# TinyTony_ShenzenReady.net
KiCad netlist of a schematic drawn in EAGLE
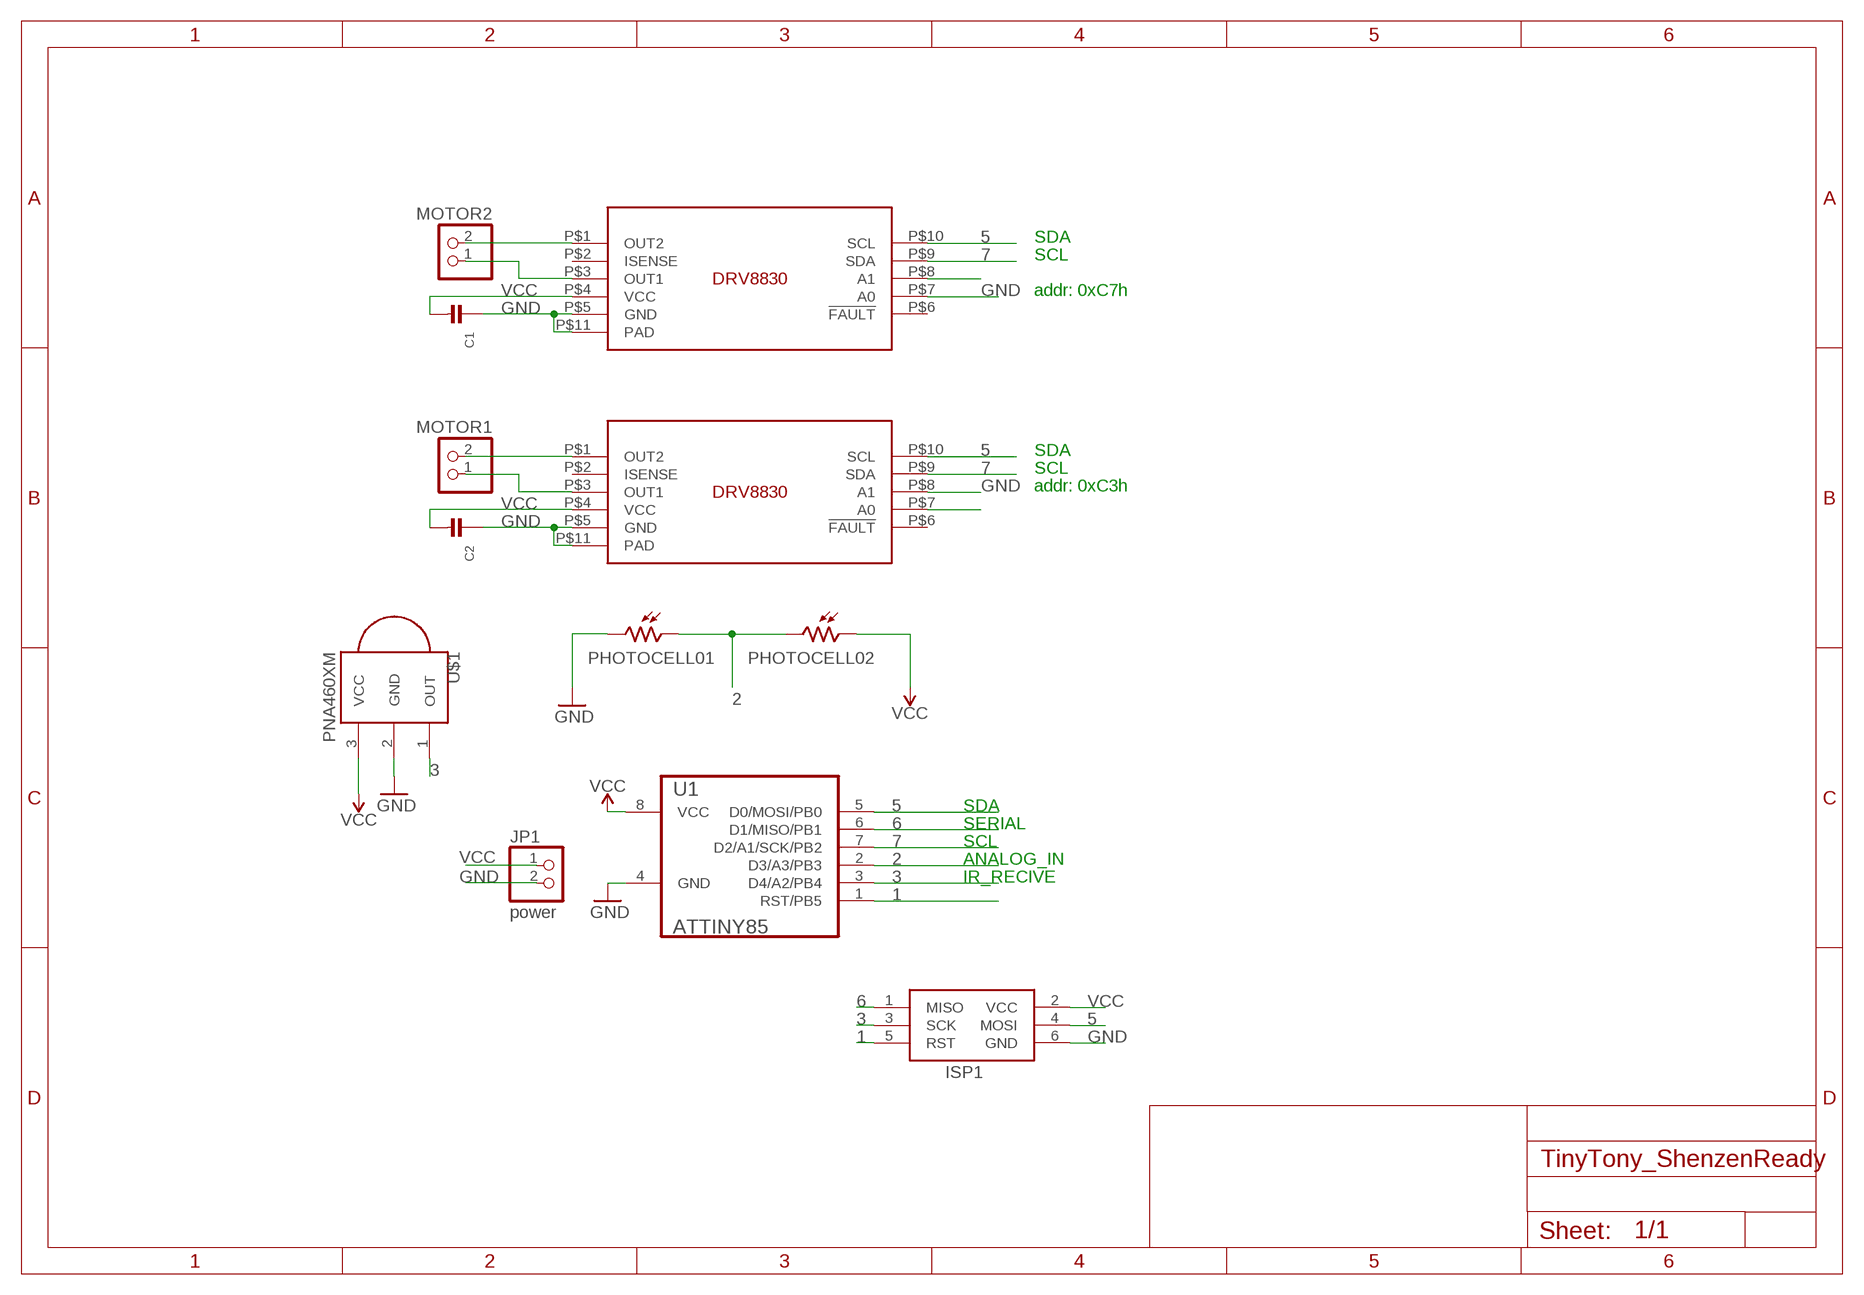
[diagram p0: schematic, sheet 1]

(export (version "E")
  (design (tool "Eeschema 10.0.6"))
  (components
    (comp (ref "C1")
      (value "CAP_CERAMIC1206")
      (footprint "eagle-import:1206")
      (libsource (lib "eagle-import") (part "CAP_CERAMIC1206"))
    )
    (comp (ref "C2")
      (value "CAP_CERAMIC1206")
      (footprint "eagle-import:1206")
      (libsource (lib "eagle-import") (part "CAP_CERAMIC1206"))
    )
    (comp (ref "ISP1")
      (value "AVRISPPOGO")
      (footprint "eagle-import:AVRISP-50MIL")
      (libsource (lib "eagle-import") (part "AVRISPPOGO"))
    )
    (comp (ref "JP1")
      (value "power")
      (footprint "eagle-import:1X02_ROUND")
      (libsource (lib "eagle-import") (part "HEADER-1X2ROUND"))
    )
    (comp (ref "JP2")
      (value "MOTOR1")
      (footprint "eagle-import:1X02_ROUND")
      (libsource (lib "eagle-import") (part "HEADER-1X2ROUND"))
    )
    (comp (ref "JP3")
      (value "MOTOR2")
      (footprint "eagle-import:1X02_ROUND")
      (libsource (lib "eagle-import") (part "HEADER-1X2ROUND"))
    )
    (comp (ref "PHOTOCELL01")
      (value "PHOTOCELL0N1")
      (footprint "eagle-import:TO46-VT200")
      (libsource (lib "eagle-import") (part "PHOTOCELL0N1"))
    )
    (comp (ref "PHOTOCELL02")
      (value "PHOTOCELL0N1")
      (footprint "eagle-import:TO46-VT200")
      (libsource (lib "eagle-import") (part "PHOTOCELL0N1"))
    )
    (comp (ref "U$1")
      (value "PNA460XM")
      (footprint "eagle-import:PNA460XM")
      (libsource (lib "eagle-import") (part "PNA460XM"))
    )
    (comp (ref "U$2")
      (value "DRV8830")
      (footprint "eagle-import:DRV8830")
      (libsource (lib "eagle-import") (part "DRV8830"))
    )
    (comp (ref "U$3")
      (value "DRV8830")
      (footprint "eagle-import:DRV8830")
      (libsource (lib "eagle-import") (part "DRV8830"))
    )
    (comp (ref "U1")
      (value "ATTINY85")
      (footprint "eagle-import:SOIC127P798X216-8N")
      (fields (field (name "MPN") "ATTINY85-20SU"))
      (libsource (lib "eagle-import") (part "ATTINY85-20SU"))
    )
  )
  (nets
    (net (code "1") (name "/1") (class "Default")
      (node (ref "ISP1") (pin "5") (pinfunction "RST_5") (pintype "output"))
      (node (ref "U1") (pin "1") (pinfunction "RST/PB5_1") (pintype "bidirectional"))
    )
    (net (code "2") (name "/2") (class "Default")
      (node (ref "PHOTOCELL01") (pin "1") (pinfunction "1_1") (pintype "passive"))
      (node (ref "PHOTOCELL02") (pin "2") (pinfunction "2_2") (pintype "passive"))
      (node (ref "U1") (pin "2") (pinfunction "D3/A3/PB3_2") (pintype "bidirectional"))
    )
    (net (code "3") (name "/3") (class "Default")
      (node (ref "ISP1") (pin "3") (pinfunction "SCK_3") (pintype "output"))
      (node (ref "U$1") (pin "1") (pinfunction "OUT_1") (pintype "output"))
      (node (ref "U1") (pin "3") (pinfunction "D4/A2/PB4_3") (pintype "bidirectional"))
    )
    (net (code "4") (name "/5") (class "Default")
      (node (ref "ISP1") (pin "4") (pinfunction "MOSI_4") (pintype "output"))
      (node (ref "U$2") (pin "P$10") (pinfunction "SCL_P$10") (pintype "bidirectional"))
      (node (ref "U$3") (pin "P$10") (pinfunction "SCL_P$10") (pintype "bidirectional"))
      (node (ref "U1") (pin "5") (pinfunction "D0/MOSI/PB0_5") (pintype "bidirectional"))
    )
    (net (code "5") (name "/6") (class "Default")
      (node (ref "ISP1") (pin "1") (pinfunction "MISO_1") (pintype "input"))
      (node (ref "U1") (pin "6") (pinfunction "D1/MISO/PB1_6") (pintype "bidirectional"))
    )
    (net (code "6") (name "/7") (class "Default")
      (node (ref "U$2") (pin "P$9") (pinfunction "SDA_P$9") (pintype "bidirectional"))
      (node (ref "U$3") (pin "P$9") (pinfunction "SDA_P$9") (pintype "bidirectional"))
      (node (ref "U1") (pin "7") (pinfunction "D2/A1/SCK/PB2_7") (pintype "bidirectional"))
    )
    (net (code "7") (name "GND") (class "Default")
      (node (ref "C1") (pin "1") (pinfunction "P$1_1") (pintype "passive"))
      (node (ref "C2") (pin "1") (pinfunction "P$1_1") (pintype "passive"))
      (node (ref "ISP1") (pin "6") (pinfunction "GND_6") (pintype "power_in"))
      (node (ref "JP1") (pin "2") (pinfunction "2_2") (pintype "passive"))
      (node (ref "PHOTOCELL01") (pin "2") (pinfunction "2_2") (pintype "passive"))
      (node (ref "U$1") (pin "2") (pinfunction "GND_2") (pintype "power_in"))
      (node (ref "U$2") (pin "P$11") (pinfunction "PAD_P$11") (pintype "bidirectional"))
      (node (ref "U$2") (pin "P$5") (pinfunction "GND_P$5") (pintype "bidirectional"))
      (node (ref "U$2") (pin "P$8") (pinfunction "A1_P$8") (pintype "bidirectional"))
      (node (ref "U$3") (pin "P$11") (pinfunction "PAD_P$11") (pintype "bidirectional"))
      (node (ref "U$3") (pin "P$5") (pinfunction "GND_P$5") (pintype "bidirectional"))
      (node (ref "U$3") (pin "P$7") (pinfunction "A0_P$7") (pintype "bidirectional"))
      (node (ref "U1") (pin "4") (pinfunction "GND_4") (pintype "passive"))
    )
    (net (code "8") (name "Net-(U$2-OUT1)") (class "Default")
      (node (ref "JP2") (pin "1") (pinfunction "1_1") (pintype "passive"))
      (node (ref "U$2") (pin "P$3") (pinfunction "OUT1_P$3") (pintype "bidirectional"))
    )
    (net (code "9") (name "Net-(U$2-OUT2)") (class "Default")
      (node (ref "JP2") (pin "2") (pinfunction "2_2") (pintype "passive"))
      (node (ref "U$2") (pin "P$1") (pinfunction "OUT2_P$1") (pintype "bidirectional"))
    )
    (net (code "10") (name "Net-(U$3-OUT1)") (class "Default")
      (node (ref "JP3") (pin "1") (pinfunction "1_1") (pintype "passive"))
      (node (ref "U$3") (pin "P$3") (pinfunction "OUT1_P$3") (pintype "bidirectional"))
    )
    (net (code "11") (name "Net-(U$3-OUT2)") (class "Default")
      (node (ref "JP3") (pin "2") (pinfunction "2_2") (pintype "passive"))
      (node (ref "U$3") (pin "P$1") (pinfunction "OUT2_P$1") (pintype "bidirectional"))
    )
    (net (code "12") (name "VCC") (class "Default")
      (node (ref "C1") (pin "2") (pinfunction "P$2_2") (pintype "passive"))
      (node (ref "C2") (pin "2") (pinfunction "P$2_2") (pintype "passive"))
      (node (ref "ISP1") (pin "2") (pinfunction "VCC_2") (pintype "power_in"))
      (node (ref "JP1") (pin "1") (pinfunction "1_1") (pintype "passive"))
      (node (ref "PHOTOCELL02") (pin "1") (pinfunction "1_1") (pintype "passive"))
      (node (ref "U$1") (pin "3") (pinfunction "VCC_3") (pintype "power_in"))
      (node (ref "U$2") (pin "P$4") (pinfunction "VCC_P$4") (pintype "bidirectional"))
      (node (ref "U$3") (pin "P$4") (pinfunction "VCC_P$4") (pintype "bidirectional"))
      (node (ref "U1") (pin "8") (pinfunction "VCC_8") (pintype "power_in"))
    )
    (net (code "13") (name "unconnected-(U$2-A0-PadP$7)") (class "Default")
      (node (ref "U$2") (pin "P$7") (pinfunction "A0_P$7") (pintype "bidirectional"))
    )
    (net (code "14") (name "unconnected-(U$2-ISENSE-PadP$2)") (class "Default")
      (node (ref "U$2") (pin "P$2") (pinfunction "ISENSE_P$2") (pintype "bidirectional"))
    )
    (net (code "15") (name "unconnected-(U$2-~{FAULT}-PadP$6)") (class "Default")
      (node (ref "U$2") (pin "P$6") (pinfunction "~{FAULT}_P$6") (pintype "bidirectional"))
    )
    (net (code "16") (name "unconnected-(U$3-A1-PadP$8)") (class "Default")
      (node (ref "U$3") (pin "P$8") (pinfunction "A1_P$8") (pintype "bidirectional"))
    )
    (net (code "17") (name "unconnected-(U$3-ISENSE-PadP$2)") (class "Default")
      (node (ref "U$3") (pin "P$2") (pinfunction "ISENSE_P$2") (pintype "bidirectional"))
    )
    (net (code "18") (name "unconnected-(U$3-~{FAULT}-PadP$6)") (class "Default")
      (node (ref "U$3") (pin "P$6") (pinfunction "~{FAULT}_P$6") (pintype "bidirectional"))
    )
  )
)
